# eCore_Power.net
KiCad netlist of a schematic drawn in Altium Designer
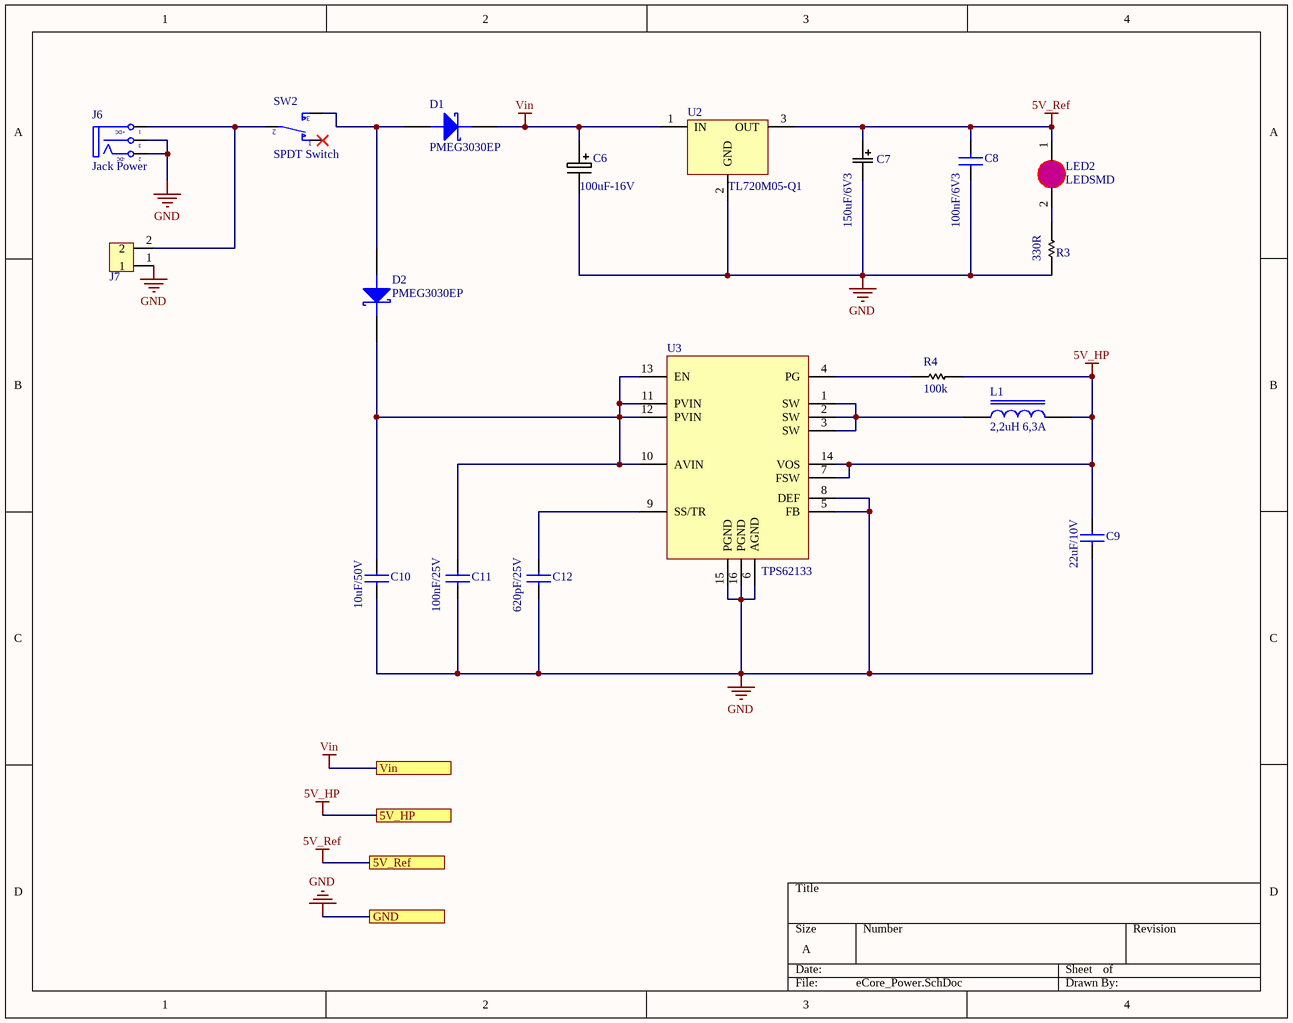
[diagram p0: eCore_Power.SchDoc]

(export (version "E")
  (design (tool "Eeschema 10.0.6"))
  (components
    (comp (ref "C6")
      (value "100uF-16V")
      (footprint "PANACAP-D-GENERIC")
      (description "GENERIC CAPACITOR POLARISED")
      (libsource (lib "SCHP-CAD") (part "PANACAP-100UF-16V-FK"))
    )
    (comp (ref "C7")
      (value "150uF/6V3")
      (footprint "CASE_B_3528_1411")
      (libsource (lib "SCHP-CAD") (part "Cap CASE B"))
    )
    (comp (ref "C8")
      (value "100nF/6V3")
      (footprint "CAPC1005X60N")
      (libsource (lib "SCHP-CAD") (part "Cap 0402"))
    )
    (comp (ref "C9") (value "22uF/10V") (footprint "C1206") (libsource (lib "SCHP-CAD") (part "Cap 1206")))
    (comp (ref "C10") (value "10uF/50V") (footprint "C1206") (libsource (lib "SCHP-CAD") (part "Cap 1206")))
    (comp (ref "C11") (value "100nF/25V") (footprint "C0603") (libsource (lib "SCHP-CAD") (part "Cap 0603")))
    (comp (ref "C12") (value "620pF/25V") (footprint "C0603") (libsource (lib "SCHP-CAD") (part "Cap 0603")))
    (comp (ref "D1")
      (value "PMEG3030EP")
      (footprint "SOD128")
      (libsource (lib "SCHP-CAD") (part "PMEG3030EP"))
    )
    (comp (ref "D2")
      (value "PMEG3030EP")
      (footprint "SOD128")
      (libsource (lib "SCHP-CAD") (part "PMEG3030EP"))
    )
    (comp (ref "J6")
      (value "Jack Power")
      (footprint "DC-IN")
      (description "Jac DC input")
      (libsource (lib "SCHP-CAD") (part "Jack Power"))
    )
    (comp (ref "J7")
      (value "Header 2x1")
      (footprint "2P ZH1.5MM")
      (libsource (lib "SCHP-CAD") (part "Header 2x1"))
    )
    (comp (ref "L1")
      (value "2,2uH 6,3A")
      (footprint "SRN8040")
      (libsource (lib "SCHP-CAD") (part "Inductor SMD"))
    )
    (comp (ref "LED2")
      (value "LEDSMD")
      (footprint "LEDR-0402")
      (description "LED 3mm")
      (libsource (lib "SCHP-CAD") (part "LEDSMD"))
    )
    (comp (ref "R3")
      (value "330R")
      (footprint "RES 0402 SMD")
      (description "Resistor")
      (fields
        (field (name "MANUFACTURER") "Generic Components")
        (field (name "PUBLISHER") "Altium Hobart Technology Centre")
      )
      (libsource (lib "SCHP-CAD") (part "Res 0402"))
    )
    (comp (ref "R4")
      (value "100k")
      (footprint "RES 0402 SMD")
      (description "Resistor")
      (fields
        (field (name "MANUFACTURER") "Generic Components")
        (field (name "PUBLISHER") "Altium Hobart Technology Centre")
      )
      (libsource (lib "SCHP-CAD") (part "Res 0402"))
    )
    (comp (ref "SW2")
      (value "SPDT Switch")
      (footprint "Slide Switch SPDT")
      (libsource (lib "SCHP-CAD") (part "SPDT Switch"))
    )
    (comp (ref "U2")
      (value "TL720M05-Q1")
      (footprint "TO-252")
      (libsource (lib "SCHP-CAD") (part "TL720M05-Q1"))
    )
    (comp (ref "U3") (value "TPS62133") (footprint "QFN16") (libsource (lib "SCHP-CAD") (part "TPS62133")))
  )
  (nets
    (net (code "1") (name "5V_HP") (class "Default")
      (node (ref "C9") (pin "1") (pinfunction "1_1") (pintype "passive"))
      (node (ref "L1") (pin "2") (pinfunction "2_2") (pintype "passive"))
      (node (ref "R4") (pin "1") (pinfunction "1_1") (pintype "passive"))
      (node (ref "U3") (pin "14") (pinfunction "VOS_14") (pintype "passive"))
      (node (ref "U3") (pin "7") (pinfunction "FSW_7") (pintype "passive"))
    )
    (net (code "2") (name "5V_Ref") (class "Default")
      (node (ref "C7") (pin "1") (pinfunction "C1_1") (pintype "passive"))
      (node (ref "C8") (pin "2") (pinfunction "2_2") (pintype "passive"))
      (node (ref "LED2") (pin "1") (pinfunction "A_1") (pintype "passive"))
      (node (ref "U2") (pin "3") (pinfunction "OUT_3") (pintype "passive"))
    )
    (net (code "3") (name "GND") (class "Default")
      (node (ref "C10") (pin "2") (pinfunction "2_2") (pintype "passive"))
      (node (ref "C11") (pin "2") (pinfunction "2_2") (pintype "passive"))
      (node (ref "C12") (pin "2") (pinfunction "2_2") (pintype "passive"))
      (node (ref "C6") (pin "-") (pinfunction "-_-") (pintype "passive"))
      (node (ref "C7") (pin "2") (pinfunction "C2_2") (pintype "passive"))
      (node (ref "C8") (pin "1") (pinfunction "1_1") (pintype "passive"))
      (node (ref "C9") (pin "2") (pinfunction "2_2") (pintype "passive"))
      (node (ref "J6") (pin "2") (pinfunction "TN_2") (pintype "passive"))
      (node (ref "J6") (pin "3") (pinfunction "S_3") (pintype "power_in"))
      (node (ref "J7") (pin "1") (pinfunction "1_1") (pintype "passive"))
      (node (ref "R3") (pin "2") (pinfunction "2_2") (pintype "passive"))
      (node (ref "U2") (pin "2") (pinfunction "GND_2") (pintype "passive"))
      (node (ref "U3") (pin "15") (pinfunction "PGND_15") (pintype "passive"))
      (node (ref "U3") (pin "16") (pinfunction "PGND_16") (pintype "passive"))
      (node (ref "U3") (pin "5") (pinfunction "FB_5") (pintype "passive"))
      (node (ref "U3") (pin "6") (pinfunction "AGND_6") (pintype "passive"))
      (node (ref "U3") (pin "8") (pinfunction "DEF_8") (pintype "passive"))
    )
    (net (code "4") (name "Net-(D1-PadA)") (class "Default")
      (node (ref "D1") (pin "A") (pinfunction "A_A") (pintype "passive"))
      (node (ref "D2") (pin "A") (pinfunction "A_A") (pintype "passive"))
      (node (ref "SW2") (pin "3") (pinfunction "3_3") (pintype "passive"))
    )
    (net (code "5") (name "Net-(J6-T)") (class "Default")
      (node (ref "J6") (pin "1") (pinfunction "T_1") (pintype "passive"))
      (node (ref "J7") (pin "2") (pinfunction "2_2") (pintype "passive"))
      (node (ref "SW2") (pin "2") (pinfunction "2_2") (pintype "passive"))
    )
    (net (code "6") (name "Net-(L1-Pad1)") (class "Default")
      (node (ref "L1") (pin "1") (pinfunction "1_1") (pintype "passive"))
      (node (ref "U3") (pin "1") (pinfunction "SW_1") (pintype "passive"))
      (node (ref "U3") (pin "2") (pinfunction "SW_2") (pintype "passive"))
      (node (ref "U3") (pin "3") (pinfunction "SW_3") (pintype "passive"))
    )
    (net (code "7") (name "Net-(LED2-K)") (class "Default")
      (node (ref "LED2") (pin "2") (pinfunction "K_2") (pintype "passive"))
      (node (ref "R3") (pin "1") (pinfunction "1_1") (pintype "passive"))
    )
    (net (code "8") (name "Net-(U3-AVIN)") (class "Default")
      (node (ref "C10") (pin "1") (pinfunction "1_1") (pintype "passive"))
      (node (ref "C11") (pin "1") (pinfunction "1_1") (pintype "passive"))
      (node (ref "D2") (pin "K") (pinfunction "K_K") (pintype "passive"))
      (node (ref "U3") (pin "10") (pinfunction "AVIN_10") (pintype "passive"))
      (node (ref "U3") (pin "11") (pinfunction "PVIN_11") (pintype "passive"))
      (node (ref "U3") (pin "12") (pinfunction "PVIN_12") (pintype "passive"))
      (node (ref "U3") (pin "13") (pinfunction "EN_13") (pintype "passive"))
    )
    (net (code "9") (name "Net-(U3-PG)") (class "Default")
      (node (ref "R4") (pin "2") (pinfunction "2_2") (pintype "passive"))
      (node (ref "U3") (pin "4") (pinfunction "PG_4") (pintype "passive"))
    )
    (net (code "10") (name "Net-(U3-SS{slash}TR)") (class "Default")
      (node (ref "C12") (pin "1") (pinfunction "1_1") (pintype "passive"))
      (node (ref "U3") (pin "9") (pinfunction "SS/TR_9") (pintype "passive"))
    )
    (net (code "11") (name "Vin") (class "Default")
      (node (ref "C6") (pin "+") (pinfunction "+_+") (pintype "passive"))
      (node (ref "D1") (pin "K") (pinfunction "K_K") (pintype "passive"))
      (node (ref "U2") (pin "1") (pinfunction "IN_1") (pintype "passive"))
    )
    (net (code "12") (name "unconnected-(SW2-Pad1)") (class "Default")
      (node (ref "SW2") (pin "1") (pinfunction "1_1") (pintype "passive+no_connect"))
    )
  )
)
